# Unit.net
KiCad netlist of a schematic drawn in Altium Designer
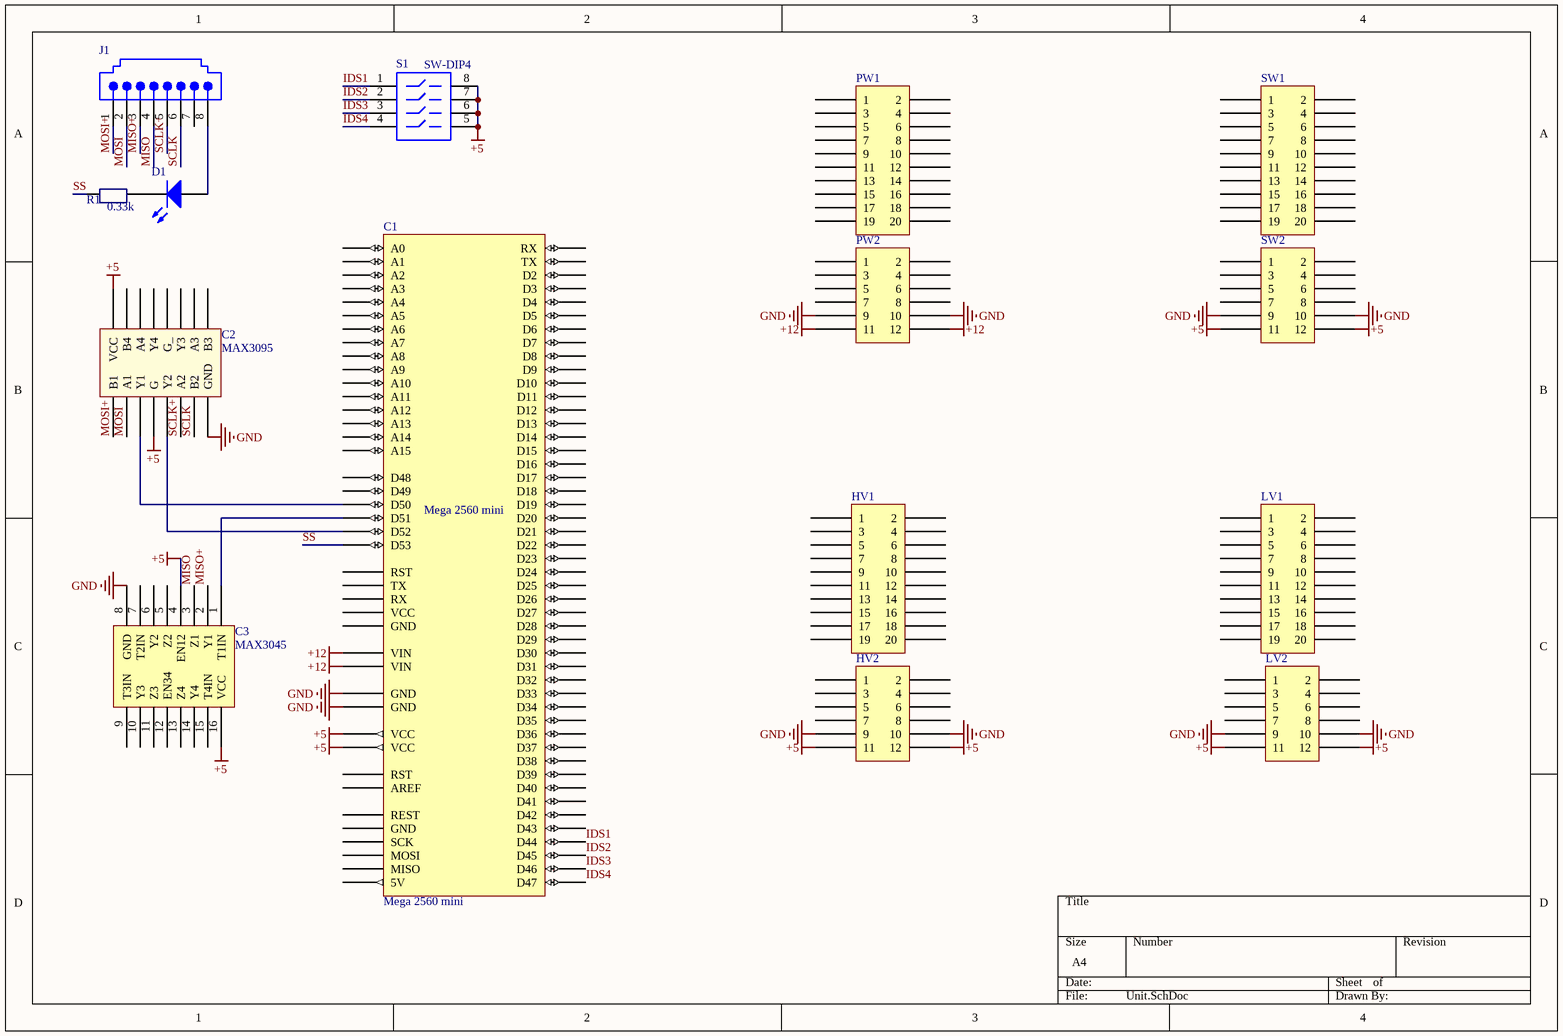
[diagram p0: Unit.SchDoc]

(export (version "E")
  (design (tool "Eeschema 10.0.6"))
  (components
    (comp (ref "C1")
      (value "Mega 2560 mini")
      (footprint "Mega 2560 mini")
      (libsource (lib "DeersADLib") (part "Mega 2560 mini"))
    )
    (comp (ref "C2") (value "MAX3095") (footprint "SOP16") (libsource (lib "DeersADLib") (part "MAX3095")))
    (comp (ref "C3")
      (value "MAX3045")
      (footprint "DeersADLib:TSSOP-16")
      (libsource (lib "DeersADLib") (part "MAX3045"))
    )
    (comp (ref "D1")
      (value "LED3")
      (footprint "3.5X2.8X1.9")
      (description "Typical BLUE SiC LED")
      (fields (field (name "PUBLISHER") "Altium Limited"))
      (libsource (lib "Miscellaneous Devices") (part "LED3"))
    )
    (comp (ref "HV1")
      (value "BTB-805-20P")
      (footprint "BTB-805-20P")
      (libsource (lib "DeersADLib") (part "BTB-805-20P"))
    )
    (comp (ref "HV2")
      (value "BTB-805-12P")
      (footprint "BTB-805-12P")
      (libsource (lib "DeersADLib") (part "BTB-805-12P"))
    )
    (comp (ref "J1")
      (value "15-43-6233")
      (footprint "15-43-6233")
      (description "Right Angle, Standard Profile, RJ45-Keyed, Flange Mount PCB Jack")
      (fields (field (name "PUBLISHER") "Altium Limited"))
      (libsource (lib "Molex Modular Jack Right Angle") (part "15-43-6233"))
    )
    (comp (ref "LV1")
      (value "BTB-805-20P")
      (footprint "BTB-805-20P")
      (libsource (lib "DeersADLib") (part "BTB-805-20P"))
    )
    (comp (ref "LV2")
      (value "BTB-805-12P")
      (footprint "BTB-805-12P")
      (libsource (lib "DeersADLib") (part "BTB-805-12P"))
    )
    (comp (ref "PW1")
      (value "BTB-805-20P")
      (footprint "BTB-805-20P")
      (libsource (lib "DeersADLib") (part "BTB-805-20P"))
    )
    (comp (ref "PW2")
      (value "BTB-805-12P")
      (footprint "BTB-805-12P")
      (libsource (lib "DeersADLib") (part "BTB-805-12P"))
    )
    (comp (ref "R1")
      (value "0.33k")
      (footprint "R0805")
      (libsource (lib "Common Device") (part "Resistance"))
    )
    (comp (ref "S1")
      (value "SW-DIP4")
      (footprint "DIP-8")
      (description "DIP Switch")
      (fields (field (name "PUBLISHER") "Altium Limited"))
      (libsource (lib "Miscellaneous Devices") (part "SW-DIP4"))
    )
    (comp (ref "SW1")
      (value "BTB-805-20P")
      (footprint "BTB-805-20P")
      (libsource (lib "DeersADLib") (part "BTB-805-20P"))
    )
    (comp (ref "SW2")
      (value "BTB-805-12P")
      (footprint "BTB-805-12P")
      (libsource (lib "DeersADLib") (part "BTB-805-12P"))
    )
  )
  (nets
    (net (code "1") (name "+5") (class "Default")
      (node (ref "C1") (pin "77") (pinfunction "VCC_77") (pintype "output"))
      (node (ref "C1") (pin "78") (pinfunction "VCC_78") (pintype "output"))
      (node (ref "C2") (pin "16") (pinfunction "VCC_16") (pintype "passive"))
      (node (ref "C2") (pin "4") (pinfunction "G_4") (pintype "passive"))
      (node (ref "C3") (pin "16") (pinfunction "VCC_16") (pintype "passive"))
      (node (ref "C3") (pin "4") (pinfunction "EN12_4") (pintype "passive"))
      (node (ref "HV2") (pin "11") (pinfunction "11_11") (pintype "passive"))
      (node (ref "HV2") (pin "12") (pinfunction "12_12") (pintype "passive"))
      (node (ref "LV2") (pin "11") (pinfunction "11_11") (pintype "passive"))
      (node (ref "LV2") (pin "12") (pinfunction "12_12") (pintype "passive"))
      (node (ref "S1") (pin "5") (pinfunction "5_5") (pintype "passive"))
      (node (ref "S1") (pin "6") (pinfunction "6_6") (pintype "passive"))
      (node (ref "S1") (pin "7") (pinfunction "7_7") (pintype "passive"))
      (node (ref "S1") (pin "8") (pinfunction "8_8") (pintype "passive"))
      (node (ref "SW2") (pin "11") (pinfunction "11_11") (pintype "passive"))
      (node (ref "SW2") (pin "12") (pinfunction "12_12") (pintype "passive"))
    )
    (net (code "2") (name "+12") (class "Default")
      (node (ref "C1") (pin "81") (pinfunction "VIN_81") (pintype "power_in"))
      (node (ref "C1") (pin "82") (pinfunction "VIN_82") (pintype "power_in"))
      (node (ref "PW2") (pin "11") (pinfunction "11_11") (pintype "passive"))
      (node (ref "PW2") (pin "12") (pinfunction "12_12") (pintype "passive"))
    )
    (net (code "3") (name "/IDS1") (class "Default")
      (node (ref "C1") (pin "60") (pinfunction "D44_60") (pintype "bidirectional"))
      (node (ref "S1") (pin "1") (pinfunction "1_1") (pintype "passive"))
    )
    (net (code "4") (name "/IDS2") (class "Default")
      (node (ref "C1") (pin "61") (pinfunction "D45_61") (pintype "bidirectional"))
      (node (ref "S1") (pin "2") (pinfunction "2_2") (pintype "passive"))
    )
    (net (code "5") (name "/IDS3") (class "Default")
      (node (ref "C1") (pin "62") (pinfunction "D46_62") (pintype "bidirectional"))
      (node (ref "S1") (pin "3") (pinfunction "3_3") (pintype "passive"))
    )
    (net (code "6") (name "/IDS4") (class "Default")
      (node (ref "C1") (pin "63") (pinfunction "D47_63") (pintype "bidirectional"))
      (node (ref "S1") (pin "4") (pinfunction "4_4") (pintype "passive"))
    )
    (net (code "7") (name "/MISO") (class "Default")
      (node (ref "C3") (pin "3") (pinfunction "Z1_3") (pintype "passive"))
      (node (ref "J1") (pin "4") (pinfunction "4_4") (pintype "passive"))
    )
    (net (code "8") (name "/MISO+") (class "Default")
      (node (ref "C3") (pin "2") (pinfunction "Y1_2") (pintype "passive"))
      (node (ref "J1") (pin "3") (pinfunction "3_3") (pintype "passive"))
    )
    (net (code "9") (name "/MOSI") (class "Default")
      (node (ref "C2") (pin "2") (pinfunction "A1_2") (pintype "passive"))
      (node (ref "J1") (pin "2") (pinfunction "2_2") (pintype "passive"))
    )
    (net (code "10") (name "/MOSI+") (class "Default")
      (node (ref "C2") (pin "1") (pinfunction "B1_1") (pintype "passive"))
      (node (ref "J1") (pin "1") (pinfunction "1_1") (pintype "passive"))
    )
    (net (code "11") (name "/SCLK") (class "Default")
      (node (ref "C2") (pin "7") (pinfunction "B2_7") (pintype "passive"))
      (node (ref "J1") (pin "6") (pinfunction "6_6") (pintype "passive"))
    )
    (net (code "12") (name "/SCLK+") (class "Default")
      (node (ref "C2") (pin "6") (pinfunction "A2_6") (pintype "passive"))
      (node (ref "J1") (pin "5") (pinfunction "5_5") (pintype "passive"))
    )
    (net (code "13") (name "/SS") (class "Default")
      (node (ref "C1") (pin "88") (pinfunction "D53_88") (pintype "bidirectional"))
      (node (ref "R1") (pin "1") (pintype "passive"))
    )
    (net (code "14") (name "GND") (class "Default")
      (node (ref "C1") (pin "79") (pinfunction "GND_79") (pintype "power_in"))
      (node (ref "C1") (pin "80") (pinfunction "GND_80") (pintype "power_in"))
      (node (ref "C2") (pin "8") (pinfunction "GND_8") (pintype "passive"))
      (node (ref "C3") (pin "8") (pinfunction "GND_8") (pintype "passive"))
      (node (ref "HV2") (pin "10") (pinfunction "10_10") (pintype "passive"))
      (node (ref "HV2") (pin "9") (pinfunction "9_9") (pintype "passive"))
      (node (ref "LV2") (pin "10") (pinfunction "10_10") (pintype "passive"))
      (node (ref "LV2") (pin "9") (pinfunction "9_9") (pintype "passive"))
      (node (ref "PW2") (pin "10") (pinfunction "10_10") (pintype "passive"))
      (node (ref "PW2") (pin "9") (pinfunction "9_9") (pintype "passive"))
      (node (ref "SW2") (pin "10") (pinfunction "10_10") (pintype "passive"))
      (node (ref "SW2") (pin "9") (pinfunction "9_9") (pintype "passive"))
    )
    (net (code "15") (name "Net-(C1-D50)") (class "Default")
      (node (ref "C1") (pin "85") (pinfunction "D50_85") (pintype "bidirectional"))
      (node (ref "C2") (pin "3") (pinfunction "Y1_3") (pintype "passive"))
    )
    (net (code "16") (name "Net-(C1-D51)") (class "Default")
      (node (ref "C1") (pin "86") (pinfunction "D51_86") (pintype "bidirectional"))
      (node (ref "C3") (pin "1") (pinfunction "T1IN_1") (pintype "passive"))
    )
    (net (code "17") (name "Net-(C1-D52)") (class "Default")
      (node (ref "C1") (pin "87") (pinfunction "D52_87") (pintype "bidirectional"))
      (node (ref "C2") (pin "5") (pinfunction "Y2_5") (pintype "passive"))
    )
    (net (code "18") (name "Net-(D1-A)") (class "Default")
      (node (ref "D1") (pin "1") (pinfunction "A_1") (pintype "passive"))
      (node (ref "J1") (pin "8") (pinfunction "8_8") (pintype "passive"))
    )
    (net (code "19") (name "Net-(D1-K)") (class "Default")
      (node (ref "D1") (pin "2") (pinfunction "K_2") (pintype "passive"))
      (node (ref "R1") (pin "2") (pintype "passive"))
    )
    (net (code "20") (name "unconnected-(C1-5V-Pad69)") (class "Default")
      (node (ref "C1") (pin "69") (pinfunction "5V_69") (pintype "output"))
    )
    (net (code "21") (name "unconnected-(C1-A0-Pad0)") (class "Default")
      (node (ref "C1") (pin "0") (pinfunction "A0_0") (pintype "bidirectional"))
    )
    (net (code "22") (name "unconnected-(C1-A1-Pad1)") (class "Default")
      (node (ref "C1") (pin "1") (pinfunction "A1_1") (pintype "bidirectional"))
    )
    (net (code "23") (name "unconnected-(C1-A2-Pad2)") (class "Default")
      (node (ref "C1") (pin "2") (pinfunction "A2_2") (pintype "bidirectional"))
    )
    (net (code "24") (name "unconnected-(C1-A3-Pad3)") (class "Default")
      (node (ref "C1") (pin "3") (pinfunction "A3_3") (pintype "bidirectional"))
    )
    (net (code "25") (name "unconnected-(C1-A4-Pad4)") (class "Default")
      (node (ref "C1") (pin "4") (pinfunction "A4_4") (pintype "bidirectional"))
    )
    (net (code "26") (name "unconnected-(C1-A5-Pad5)") (class "Default")
      (node (ref "C1") (pin "5") (pinfunction "A5_5") (pintype "bidirectional"))
    )
    (net (code "27") (name "unconnected-(C1-A6-Pad6)") (class "Default")
      (node (ref "C1") (pin "6") (pinfunction "A6_6") (pintype "bidirectional"))
    )
    (net (code "28") (name "unconnected-(C1-A7-Pad7)") (class "Default")
      (node (ref "C1") (pin "7") (pinfunction "A7_7") (pintype "bidirectional"))
    )
    (net (code "29") (name "unconnected-(C1-A8-Pad8)") (class "Default")
      (node (ref "C1") (pin "8") (pinfunction "A8_8") (pintype "bidirectional"))
    )
    (net (code "30") (name "unconnected-(C1-A9-Pad9)") (class "Default")
      (node (ref "C1") (pin "9") (pinfunction "A9_9") (pintype "bidirectional"))
    )
    (net (code "31") (name "unconnected-(C1-A10-Pad10)") (class "Default")
      (node (ref "C1") (pin "10") (pinfunction "A10_10") (pintype "bidirectional"))
    )
    (net (code "32") (name "unconnected-(C1-A11-Pad11)") (class "Default")
      (node (ref "C1") (pin "11") (pinfunction "A11_11") (pintype "bidirectional"))
    )
    (net (code "33") (name "unconnected-(C1-A12-Pad12)") (class "Default")
      (node (ref "C1") (pin "12") (pinfunction "A12_12") (pintype "bidirectional"))
    )
    (net (code "34") (name "unconnected-(C1-A13-Pad13)") (class "Default")
      (node (ref "C1") (pin "13") (pinfunction "A13_13") (pintype "bidirectional"))
    )
    (net (code "35") (name "unconnected-(C1-A14-Pad14)") (class "Default")
      (node (ref "C1") (pin "14") (pinfunction "A14_14") (pintype "bidirectional"))
    )
    (net (code "36") (name "unconnected-(C1-A15-Pad15)") (class "Default")
      (node (ref "C1") (pin "15") (pinfunction "A15_15") (pintype "bidirectional"))
    )
    (net (code "37") (name "unconnected-(C1-AREF-Pad75)") (class "Default")
      (node (ref "C1") (pin "75") (pinfunction "AREF_75") (pintype "passive"))
    )
    (net (code "38") (name "unconnected-(C1-D2-Pad18)") (class "Default")
      (node (ref "C1") (pin "18") (pinfunction "D2_18") (pintype "bidirectional"))
    )
    (net (code "39") (name "unconnected-(C1-D3-Pad19)") (class "Default")
      (node (ref "C1") (pin "19") (pinfunction "D3_19") (pintype "bidirectional"))
    )
    (net (code "40") (name "unconnected-(C1-D4-Pad20)") (class "Default")
      (node (ref "C1") (pin "20") (pinfunction "D4_20") (pintype "bidirectional"))
    )
    (net (code "41") (name "unconnected-(C1-D5-Pad21)") (class "Default")
      (node (ref "C1") (pin "21") (pinfunction "D5_21") (pintype "bidirectional"))
    )
    (net (code "42") (name "unconnected-(C1-D6-Pad22)") (class "Default")
      (node (ref "C1") (pin "22") (pinfunction "D6_22") (pintype "bidirectional"))
    )
    (net (code "43") (name "unconnected-(C1-D7-Pad23)") (class "Default")
      (node (ref "C1") (pin "23") (pinfunction "D7_23") (pintype "bidirectional"))
    )
    (net (code "44") (name "unconnected-(C1-D8-Pad24)") (class "Default")
      (node (ref "C1") (pin "24") (pinfunction "D8_24") (pintype "bidirectional"))
    )
    (net (code "45") (name "unconnected-(C1-D9-Pad25)") (class "Default")
      (node (ref "C1") (pin "25") (pinfunction "D9_25") (pintype "bidirectional"))
    )
    (net (code "46") (name "unconnected-(C1-D10-Pad26)") (class "Default")
      (node (ref "C1") (pin "26") (pinfunction "D10_26") (pintype "bidirectional"))
    )
    (net (code "47") (name "unconnected-(C1-D11-Pad27)") (class "Default")
      (node (ref "C1") (pin "27") (pinfunction "D11_27") (pintype "bidirectional"))
    )
    (net (code "48") (name "unconnected-(C1-D12-Pad28)") (class "Default")
      (node (ref "C1") (pin "28") (pinfunction "D12_28") (pintype "bidirectional"))
    )
    (net (code "49") (name "unconnected-(C1-D13-Pad29)") (class "Default")
      (node (ref "C1") (pin "29") (pinfunction "D13_29") (pintype "bidirectional"))
    )
    (net (code "50") (name "unconnected-(C1-D14-Pad30)") (class "Default")
      (node (ref "C1") (pin "30") (pinfunction "D14_30") (pintype "bidirectional"))
    )
    (net (code "51") (name "unconnected-(C1-D15-Pad31)") (class "Default")
      (node (ref "C1") (pin "31") (pinfunction "D15_31") (pintype "bidirectional"))
    )
    (net (code "52") (name "unconnected-(C1-D16-Pad32)") (class "Default")
      (node (ref "C1") (pin "32") (pinfunction "D16_32") (pintype "bidirectional"))
    )
    (net (code "53") (name "unconnected-(C1-D17-Pad33)") (class "Default")
      (node (ref "C1") (pin "33") (pinfunction "D17_33") (pintype "bidirectional"))
    )
    (net (code "54") (name "unconnected-(C1-D18-Pad34)") (class "Default")
      (node (ref "C1") (pin "34") (pinfunction "D18_34") (pintype "bidirectional"))
    )
    (net (code "55") (name "unconnected-(C1-D19-Pad35)") (class "Default")
      (node (ref "C1") (pin "35") (pinfunction "D19_35") (pintype "bidirectional"))
    )
    (net (code "56") (name "unconnected-(C1-D20-Pad36)") (class "Default")
      (node (ref "C1") (pin "36") (pinfunction "D20_36") (pintype "bidirectional"))
    )
    (net (code "57") (name "unconnected-(C1-D21-Pad37)") (class "Default")
      (node (ref "C1") (pin "37") (pinfunction "D21_37") (pintype "bidirectional"))
    )
    (net (code "58") (name "unconnected-(C1-D22-Pad38)") (class "Default")
      (node (ref "C1") (pin "38") (pinfunction "D22_38") (pintype "bidirectional"))
    )
    (net (code "59") (name "unconnected-(C1-D23-Pad39)") (class "Default")
      (node (ref "C1") (pin "39") (pinfunction "D23_39") (pintype "bidirectional"))
    )
    (net (code "60") (name "unconnected-(C1-D24-Pad40)") (class "Default")
      (node (ref "C1") (pin "40") (pinfunction "D24_40") (pintype "bidirectional"))
    )
    (net (code "61") (name "unconnected-(C1-D25-Pad41)") (class "Default")
      (node (ref "C1") (pin "41") (pinfunction "D25_41") (pintype "bidirectional"))
    )
    (net (code "62") (name "unconnected-(C1-D26-Pad42)") (class "Default")
      (node (ref "C1") (pin "42") (pinfunction "D26_42") (pintype "bidirectional"))
    )
    (net (code "63") (name "unconnected-(C1-D27-Pad43)") (class "Default")
      (node (ref "C1") (pin "43") (pinfunction "D27_43") (pintype "bidirectional"))
    )
    (net (code "64") (name "unconnected-(C1-D28-Pad44)") (class "Default")
      (node (ref "C1") (pin "44") (pinfunction "D28_44") (pintype "bidirectional"))
    )
    (net (code "65") (name "unconnected-(C1-D29-Pad45)") (class "Default")
      (node (ref "C1") (pin "45") (pinfunction "D29_45") (pintype "bidirectional"))
    )
    (net (code "66") (name "unconnected-(C1-D30-Pad46)") (class "Default")
      (node (ref "C1") (pin "46") (pinfunction "D30_46") (pintype "bidirectional"))
    )
    (net (code "67") (name "unconnected-(C1-D31-Pad47)") (class "Default")
      (node (ref "C1") (pin "47") (pinfunction "D31_47") (pintype "bidirectional"))
    )
    (net (code "68") (name "unconnected-(C1-D32-Pad48)") (class "Default")
      (node (ref "C1") (pin "48") (pinfunction "D32_48") (pintype "bidirectional"))
    )
    (net (code "69") (name "unconnected-(C1-D33-Pad49)") (class "Default")
      (node (ref "C1") (pin "49") (pinfunction "D33_49") (pintype "bidirectional"))
    )
    (net (code "70") (name "unconnected-(C1-D34-Pad50)") (class "Default")
      (node (ref "C1") (pin "50") (pinfunction "D34_50") (pintype "bidirectional"))
    )
    (net (code "71") (name "unconnected-(C1-D35-Pad51)") (class "Default")
      (node (ref "C1") (pin "51") (pinfunction "D35_51") (pintype "bidirectional"))
    )
    (net (code "72") (name "unconnected-(C1-D36-Pad52)") (class "Default")
      (node (ref "C1") (pin "52") (pinfunction "D36_52") (pintype "bidirectional"))
    )
    (net (code "73") (name "unconnected-(C1-D37-Pad53)") (class "Default")
      (node (ref "C1") (pin "53") (pinfunction "D37_53") (pintype "bidirectional"))
    )
    (net (code "74") (name "unconnected-(C1-D38-Pad54)") (class "Default")
      (node (ref "C1") (pin "54") (pinfunction "D38_54") (pintype "bidirectional"))
    )
    (net (code "75") (name "unconnected-(C1-D39-Pad55)") (class "Default")
      (node (ref "C1") (pin "55") (pinfunction "D39_55") (pintype "bidirectional"))
    )
    (net (code "76") (name "unconnected-(C1-D40-Pad56)") (class "Default")
      (node (ref "C1") (pin "56") (pinfunction "D40_56") (pintype "bidirectional"))
    )
    (net (code "77") (name "unconnected-(C1-D41-Pad57)") (class "Default")
      (node (ref "C1") (pin "57") (pinfunction "D41_57") (pintype "bidirectional"))
    )
    (net (code "78") (name "unconnected-(C1-D42-Pad58)") (class "Default")
      (node (ref "C1") (pin "58") (pinfunction "D42_58") (pintype "bidirectional"))
    )
    (net (code "79") (name "unconnected-(C1-D43-Pad59)") (class "Default")
      (node (ref "C1") (pin "59") (pinfunction "D43_59") (pintype "bidirectional"))
    )
    (net (code "80") (name "unconnected-(C1-D48-Pad83)") (class "Default")
      (node (ref "C1") (pin "83") (pinfunction "D48_83") (pintype "bidirectional"))
    )
    (net (code "81") (name "unconnected-(C1-D49-Pad84)") (class "Default")
      (node (ref "C1") (pin "84") (pinfunction "D49_84") (pintype "bidirectional"))
    )
    (net (code "82") (name "unconnected-(C1-GND-Pad68)") (class "Default")
      (node (ref "C1") (pin "68") (pinfunction "GND_68") (pintype "passive"))
    )
    (net (code "83") (name "unconnected-(C1-GND-Pad73)") (class "Default")
      (node (ref "C1") (pin "73") (pinfunction "GND_73") (pintype "passive"))
    )
    (net (code "84") (name "unconnected-(C1-MISO-Pad70)") (class "Default")
      (node (ref "C1") (pin "70") (pinfunction "MISO_70") (pintype "passive"))
    )
    (net (code "85") (name "unconnected-(C1-MOSI-Pad71)") (class "Default")
      (node (ref "C1") (pin "71") (pinfunction "MOSI_71") (pintype "passive"))
    )
    (net (code "86") (name "unconnected-(C1-REST-Pad74)") (class "Default")
      (node (ref "C1") (pin "74") (pinfunction "REST_74") (pintype "passive"))
    )
    (net (code "87") (name "unconnected-(C1-RST-Pad64)") (class "Default")
      (node (ref "C1") (pin "64") (pinfunction "RST_64") (pintype "passive"))
    )
    (net (code "88") (name "unconnected-(C1-RST-Pad76)") (class "Default")
      (node (ref "C1") (pin "76") (pinfunction "RST_76") (pintype "passive"))
    )
    (net (code "89") (name "unconnected-(C1-RX-Pad16)") (class "Default")
      (node (ref "C1") (pin "16") (pinfunction "RX_16") (pintype "bidirectional"))
    )
    (net (code "90") (name "unconnected-(C1-RX-Pad66)") (class "Default")
      (node (ref "C1") (pin "66") (pinfunction "RX_66") (pintype "passive"))
    )
    (net (code "91") (name "unconnected-(C1-SCK-Pad72)") (class "Default")
      (node (ref "C1") (pin "72") (pinfunction "SCK_72") (pintype "passive"))
    )
    (net (code "92") (name "unconnected-(C1-TX-Pad17)") (class "Default")
      (node (ref "C1") (pin "17") (pinfunction "TX_17") (pintype "bidirectional"))
    )
    (net (code "93") (name "unconnected-(C1-TX-Pad65)") (class "Default")
      (node (ref "C1") (pin "65") (pinfunction "TX_65") (pintype "passive"))
    )
    (net (code "94") (name "unconnected-(C1-VCC-Pad67)") (class "Default")
      (node (ref "C1") (pin "67") (pinfunction "VCC_67") (pintype "passive"))
    )
    (net (code "95") (name "unconnected-(C2-A3-Pad10)") (class "Default")
      (node (ref "C2") (pin "10") (pinfunction "A3_10") (pintype "passive"))
    )
    (net (code "96") (name "unconnected-(C2-A4-Pad14)") (class "Default")
      (node (ref "C2") (pin "14") (pinfunction "A4_14") (pintype "passive"))
    )
    (net (code "97") (name "unconnected-(C2-B3-Pad9)") (class "Default")
      (node (ref "C2") (pin "9") (pinfunction "B3_9") (pintype "passive"))
    )
    (net (code "98") (name "unconnected-(C2-B4-Pad15)") (class "Default")
      (node (ref "C2") (pin "15") (pinfunction "B4_15") (pintype "passive"))
    )
    (net (code "99") (name "unconnected-(C2-G_-Pad12)") (class "Default")
      (node (ref "C2") (pin "12") (pinfunction "G__12") (pintype "passive"))
    )
    (net (code "100") (name "unconnected-(C2-Y3-Pad11)") (class "Default")
      (node (ref "C2") (pin "11") (pinfunction "Y3_11") (pintype "passive"))
    )
    (net (code "101") (name "unconnected-(C2-Y4-Pad13)") (class "Default")
      (node (ref "C2") (pin "13") (pinfunction "Y4_13") (pintype "passive"))
    )
    (net (code "102") (name "unconnected-(C3-EN34-Pad12)") (class "Default")
      (node (ref "C3") (pin "12") (pinfunction "EN34_12") (pintype "passive"))
    )
    (net (code "103") (name "unconnected-(C3-T2IN-Pad7)") (class "Default")
      (node (ref "C3") (pin "7") (pinfunction "T2IN_7") (pintype "passive"))
    )
    (net (code "104") (name "unconnected-(C3-T3IN-Pad9)") (class "Default")
      (node (ref "C3") (pin "9") (pinfunction "T3IN_9") (pintype "passive"))
    )
    (net (code "105") (name "unconnected-(C3-T4IN-Pad15)") (class "Default")
      (node (ref "C3") (pin "15") (pinfunction "T4IN_15") (pintype "passive"))
    )
    (net (code "106") (name "unconnected-(C3-Y2-Pad6)") (class "Default")
      (node (ref "C3") (pin "6") (pinfunction "Y2_6") (pintype "passive"))
    )
    (net (code "107") (name "unconnected-(C3-Y3-Pad10)") (class "Default")
      (node (ref "C3") (pin "10") (pinfunction "Y3_10") (pintype "passive"))
    )
    (net (code "108") (name "unconnected-(C3-Y4-Pad14)") (class "Default")
      (node (ref "C3") (pin "14") (pinfunction "Y4_14") (pintype "passive"))
    )
    (net (code "109") (name "unconnected-(C3-Z2-Pad5)") (class "Default")
      (node (ref "C3") (pin "5") (pinfunction "Z2_5") (pintype "passive"))
    )
    (net (code "110") (name "unconnected-(C3-Z3-Pad11)") (class "Default")
      (node (ref "C3") (pin "11") (pinfunction "Z3_11") (pintype "passive"))
    )
    (net (code "111") (name "unconnected-(C3-Z4-Pad13)") (class "Default")
      (node (ref "C3") (pin "13") (pinfunction "Z4_13") (pintype "passive"))
    )
    (net (code "112") (name "unconnected-(HV1-Pad1)") (class "Default")
      (node (ref "HV1") (pin "1") (pinfunction "1_1") (pintype "passive"))
    )
    (net (code "113") (name "unconnected-(HV1-Pad2)") (class "Default")
      (node (ref "HV1") (pin "2") (pinfunction "2_2") (pintype "passive"))
    )
    (net (code "114") (name "unconnected-(HV1-Pad3)") (class "Default")
      (node (ref "HV1") (pin "3") (pinfunction "3_3") (pintype "passive"))
    )
    (net (code "115") (name "unconnected-(HV1-Pad4)") (class "Default")
      (node (ref "HV1") (pin "4") (pinfunction "4_4") (pintype "passive"))
    )
    (net (code "116") (name "unconnected-(HV1-Pad5)") (class "Default")
      (node (ref "HV1") (pin "5") (pinfunction "5_5") (pintype "passive"))
    )
    (net (code "117") (name "unconnected-(HV1-Pad6)") (class "Default")
      (node (ref "HV1") (pin "6") (pinfunction "6_6") (pintype "passive"))
    )
    (net (code "118") (name "unconnected-(HV1-Pad7)") (class "Default")
      (node (ref "HV1") (pin "7") (pinfunction "7_7") (pintype "passive"))
    )
    (net (code "119") (name "unconnected-(HV1-Pad8)") (class "Default")
      (node (ref "HV1") (pin "8") (pinfunction "8_8") (pintype "passive"))
    )
    (net (code "120") (name "unconnected-(HV1-Pad9)") (class "Default")
      (node (ref "HV1") (pin "9") (pinfunction "9_9") (pintype "passive"))
    )
    (net (code "121") (name "unconnected-(HV1-Pad10)") (class "Default")
      (node (ref "HV1") (pin "10") (pinfunction "10_10") (pintype "passive"))
    )
    (net (code "122") (name "unconnected-(HV1-Pad11)") (class "Default")
      (node (ref "HV1") (pin "11") (pinfunction "11_11") (pintype "passive"))
    )
    (net (code "123") (name "unconnected-(HV1-Pad12)") (class "Default")
      (node (ref "HV1") (pin "12") (pinfunction "12_12") (pintype "passive"))
    )
    (net (code "124") (name "unconnected-(HV1-Pad13)") (class "Default")
      (node (ref "HV1") (pin "13") (pinfunction "13_13") (pintype "passive"))
    )
    (net (code "125") (name "unconnected-(HV1-Pad14)") (class "Default")
      (node (ref "HV1") (pin "14") (pinfunction "14_14") (pintype "passive"))
    )
    (net (code "126") (name "unconnected-(HV1-Pad15)") (class "Default")
      (node (ref "HV1") (pin "15") (pinfunction "15_15") (pintype "passive"))
    )
    (net (code "127") (name "unconnected-(HV1-Pad16)") (class "Default")
      (node (ref "HV1") (pin "16") (pinfunction "16_16") (pintype "passive"))
    )
    (net (code "128") (name "unconnected-(HV1-Pad17)") (class "Default")
      (node (ref "HV1") (pin "17") (pinfunction "17_17") (pintype "passive"))
    )
    (net (code "129") (name "unconnected-(HV1-Pad18)") (class "Default")
      (node (ref "HV1") (pin "18") (pinfunction "18_18") (pintype "passive"))
    )
    (net (code "130") (name "unconnected-(HV1-Pad19)") (class "Default")
      (node (ref "HV1") (pin "19") (pinfunction "19_19") (pintype "passive"))
    )
    (net (code "131") (name "unconnected-(HV1-Pad20)") (class "Default")
      (node (ref "HV1") (pin "20") (pinfunction "20_20") (pintype "passive"))
    )
    (net (code "132") (name "unconnected-(HV2-Pad1)") (class "Default")
      (node (ref "HV2") (pin "1") (pinfunction "1_1") (pintype "passive"))
    )
    (net (code "133") (name "unconnected-(HV2-Pad2)") (class "Default")
      (node (ref "HV2") (pin "2") (pinfunction "2_2") (pintype "passive"))
    )
    (net (code "134") (name "unconnected-(HV2-Pad3)") (class "Default")
      (node (ref "HV2") (pin "3") (pinfunction "3_3") (pintype "passive"))
    )
    (net (code "135") (name "unconnected-(HV2-Pad4)") (class "Default")
      (node (ref "HV2") (pin "4") (pinfunction "4_4") (pintype "passive"))
    )
    (net (code "136") (name "unconnected-(HV2-Pad5)") (class "Default")
      (node (ref "HV2") (pin "5") (pinfunction "5_5") (pintype "passive"))
    )
    (net (code "137") (name "unconnected-(HV2-Pad6)") (class "Default")
      (node (ref "HV2") (pin "6") (pinfunction "6_6") (pintype "passive"))
    )
    (net (code "138") (name "unconnected-(HV2-Pad7)") (class "Default")
      (node (ref "HV2") (pin "7") (pinfunction "7_7") (pintype "passive"))
    )
    (net (code "139") (name "unconnected-(HV2-Pad8)") (class "Default")
      (node (ref "HV2") (pin "8") (pinfunction "8_8") (pintype "passive"))
    )
    (net (code "140") (name "unconnected-(J1-Pad7)") (class "Default")
      (node (ref "J1") (pin "7") (pinfunction "7_7") (pintype "passive"))
    )
    (net (code "141") (name "unconnected-(LV1-Pad1)") (class "Default")
      (node (ref "LV1") (pin "1") (pinfunction "1_1") (pintype "passive"))
    )
    (net (code "142") (name "unconnected-(LV1-Pad2)") (class "Default")
      (node (ref "LV1") (pin "2") (pinfunction "2_2") (pintype "passive"))
    )
    (net (code "143") (name "unconnected-(LV1-Pad3)") (class "Default")
      (node (ref "LV1") (pin "3") (pinfunction "3_3") (pintype "passive"))
    )
    (net (code "144") (name "unconnected-(LV1-Pad4)") (class "Default")
      (node (ref "LV1") (pin "4") (pinfunction "4_4") (pintype "passive"))
    )
    (net (code "145") (name "unconnected-(LV1-Pad5)") (class "Default")
      (node (ref "LV1") (pin "5") (pinfunction "5_5") (pintype "passive"))
    )
    (net (code "146") (name "unconnected-(LV1-Pad6)") (class "Default")
      (node (ref "LV1") (pin "6") (pinfunction "6_6") (pintype "passive"))
    )
    (net (code "147") (name "unconnected-(LV1-Pad7)") (class "Default")
      (node (ref "LV1") (pin "7") (pinfunction "7_7") (pintype "passive"))
    )
    (net (code "148") (name "unconnected-(LV1-Pad8)") (class "Default")
      (node (ref "LV1") (pin "8") (pinfunction "8_8") (pintype "passive"))
    )
    (net (code "149") (name "unconnected-(LV1-Pad9)") (class "Default")
      (node (ref "LV1") (pin "9") (pinfunction "9_9") (pintype "passive"))
    )
    (net (code "150") (name "unconnected-(LV1-Pad10)") (class "Default")
      (node (ref "LV1") (pin "10") (pinfunction "10_10") (pintype "passive"))
    )
    (net (code "151") (name "unconnected-(LV1-Pad11)") (class "Default")
      (node (ref "LV1") (pin "11") (pinfunction "11_11") (pintype "passive"))
    )
    (net (code "152") (name "unconnected-(LV1-Pad12)") (class "Default")
      (node (ref "LV1") (pin "12") (pinfunction "12_12") (pintype "passive"))
    )
    (net (code "153") (name "unconnected-(LV1-Pad13)") (class "Default")
      (node (ref "LV1") (pin "13") (pinfunction "13_13") (pintype "passive"))
    )
    (net (code "154") (name "unconnected-(LV1-Pad14)") (class "Default")
      (node (ref "LV1") (pin "14") (pinfunction "14_14") (pintype "passive"))
    )
    (net (code "155") (name "unconnected-(LV1-Pad15)") (class "Default")
      (node (ref "LV1") (pin "15") (pinfunction "15_15") (pintype "passive"))
    )
    (net (code "156") (name "unconnected-(LV1-Pad16)") (class "Default")
      (node (ref "LV1") (pin "16") (pinfunction "16_16") (pintype "passive"))
    )
    (net (code "157") (name "unconnected-(LV1-Pad17)") (class "Default")
      (node (ref "LV1") (pin "17") (pinfunction "17_17") (pintype "passive"))
    )
    (net (code "158") (name "unconnected-(LV1-Pad18)") (class "Default")
      (node (ref "LV1") (pin "18") (pinfunction "18_18") (pintype "passive"))
    )
    (net (code "159") (name "unconnected-(LV1-Pad19)") (class "Default")
      (node (ref "LV1") (pin "19") (pinfunction "19_19") (pintype "passive"))
    )
    (net (code "160") (name "unconnected-(LV1-Pad20)") (class "Default")
      (node (ref "LV1") (pin "20") (pinfunction "20_20") (pintype "passive"))
    )
    (net (code "161") (name "unconnected-(LV2-Pad1)") (class "Default")
      (node (ref "LV2") (pin "1") (pinfunction "1_1") (pintype "passive"))
    )
    (net (code "162") (name "unconnected-(LV2-Pad2)") (class "Default")
      (node (ref "LV2") (pin "2") (pinfunction "2_2") (pintype "passive"))
    )
    (net (code "163") (name "unconnected-(LV2-Pad3)") (class "Default")
      (node (ref "LV2") (pin "3") (pinfunction "3_3") (pintype "passive"))
    )
    (net (code "164") (name "unconnected-(LV2-Pad4)") (class "Default")
      (node (ref "LV2") (pin "4") (pinfunction "4_4") (pintype "passive"))
    )
    (net (code "165") (name "unconnected-(LV2-Pad5)") (class "Default")
      (node (ref "LV2") (pin "5") (pinfunction "5_5") (pintype "passive"))
    )
    (net (code "166") (name "unconnected-(LV2-Pad6)") (class "Default")
      (node (ref "LV2") (pin "6") (pinfunction "6_6") (pintype "passive"))
    )
    (net (code "167") (name "unconnected-(LV2-Pad7)") (class "Default")
      (node (ref "LV2") (pin "7") (pinfunction "7_7") (pintype "passive"))
    )
    (net (code "168") (name "unconnected-(LV2-Pad8)") (class "Default")
      (node (ref "LV2") (pin "8") (pinfunction "8_8") (pintype "passive"))
    )
    (net (code "169") (name "unconnected-(PW1-Pad1)") (class "Default")
      (node (ref "PW1") (pin "1") (pinfunction "1_1") (pintype "passive"))
    )
    (net (code "170") (name "unconnected-(PW1-Pad2)") (class "Default")
      (node (ref "PW1") (pin "2") (pinfunction "2_2") (pintype "passive"))
    )
    (net (code "171") (name "unconnected-(PW1-Pad3)") (class "Default")
      (node (ref "PW1") (pin "3") (pinfunction "3_3") (pintype "passive"))
    )
    (net (code "172") (name "unconnected-(PW1-Pad4)") (class "Default")
      (node (ref "PW1") (pin "4") (pinfunction "4_4") (pintype "passive"))
    )
    (net (code "173") (name "unconnected-(PW1-Pad5)") (class "Default")
      (node (ref "PW1") (pin "5") (pinfunction "5_5") (pintype "passive"))
    )
    (net (code "174") (name "unconnected-(PW1-Pad6)") (class "Default")
      (node (ref "PW1") (pin "6") (pinfunction "6_6") (pintype "passive"))
    )
    (net (code "175") (name "unconnected-(PW1-Pad7)") (class "Default")
      (node (ref "PW1") (pin "7") (pinfunction "7_7") (pintype "passive"))
    )
    (net (code "176") (name "unconnected-(PW1-Pad8)") (class "Default")
      (node (ref "PW1") (pin "8") (pinfunction "8_8") (pintype "passive"))
    )
    (net (code "177") (name "unconnected-(PW1-Pad9)") (class "Default")
      (node (ref "PW1") (pin "9") (pinfunction "9_9") (pintype "passive"))
    )
    (net (code "178") (name "unconnected-(PW1-Pad10)") (class "Default")
      (node (ref "PW1") (pin "10") (pinfunction "10_10") (pintype "passive"))
    )
    (net (code "179") (name "unconnected-(PW1-Pad11)") (class "Default")
      (node (ref "PW1") (pin "11") (pinfunction "11_11") (pintype "passive"))
    )
    (net (code "180") (name "unconnected-(PW1-Pad12)") (class "Default")
      (node (ref "PW1") (pin "12") (pinfunction "12_12") (pintype "passive"))
    )
    (net (code "181") (name "unconnected-(PW1-Pad13)") (class "Default")
      (node (ref "PW1") (pin "13") (pinfunction "13_13") (pintype "passive"))
    )
    (net (code "182") (name "unconnected-(PW1-Pad14)") (class "Default")
      (node (ref "PW1") (pin "14") (pinfunction "14_14") (pintype "passive"))
    )
    (net (code "183") (name "unconnected-(PW1-Pad15)") (class "Default")
      (node (ref "PW1") (pin "15") (pinfunction "15_15") (pintype "passive"))
    )
    (net (code "184") (name "unconnected-(PW1-Pad16)") (class "Default")
      (node (ref "PW1") (pin "16") (pinfunction "16_16") (pintype "passive"))
    )
    (net (code "185") (name "unconnected-(PW1-Pad17)") (class "Default")
      (node (ref "PW1") (pin "17") (pinfunction "17_17") (pintype "passive"))
    )
    (net (code "186") (name "unconnected-(PW1-Pad18)") (class "Default")
      (node (ref "PW1") (pin "18") (pinfunction "18_18") (pintype "passive"))
    )
    (net (code "187") (name "unconnected-(PW1-Pad19)") (class "Default")
      (node (ref "PW1") (pin "19") (pinfunction "19_19") (pintype "passive"))
    )
    (net (code "188") (name "unconnected-(PW1-Pad20)") (class "Default")
      (node (ref "PW1") (pin "20") (pinfunction "20_20") (pintype "passive"))
    )
    (net (code "189") (name "unconnected-(PW2-Pad1)") (class "Default")
      (node (ref "PW2") (pin "1") (pinfunction "1_1") (pintype "passive"))
    )
    (net (code "190") (name "unconnected-(PW2-Pad2)") (class "Default")
      (node (ref "PW2") (pin "2") (pinfunction "2_2") (pintype "passive"))
    )
    (net (code "191") (name "unconnected-(PW2-Pad3)") (class "Default")
      (node (ref "PW2") (pin "3") (pinfunction "3_3") (pintype "passive"))
    )
    (net (code "192") (name "unconnected-(PW2-Pad4)") (class "Default")
      (node (ref "PW2") (pin "4") (pinfunction "4_4") (pintype "passive"))
    )
    (net (code "193") (name "unconnected-(PW2-Pad5)") (class "Default")
      (node (ref "PW2") (pin "5") (pinfunction "5_5") (pintype "passive"))
    )
    (net (code "194") (name "unconnected-(PW2-Pad6)") (class "Default")
      (node (ref "PW2") (pin "6") (pinfunction "6_6") (pintype "passive"))
    )
    (net (code "195") (name "unconnected-(PW2-Pad7)") (class "Default")
      (node (ref "PW2") (pin "7") (pinfunction "7_7") (pintype "passive"))
    )
    (net (code "196") (name "unconnected-(PW2-Pad8)") (class "Default")
      (node (ref "PW2") (pin "8") (pinfunction "8_8") (pintype "passive"))
    )
    (net (code "197") (name "unconnected-(SW1-Pad1)") (class "Default")
      (node (ref "SW1") (pin "1") (pinfunction "1_1") (pintype "passive"))
    )
    (net (code "198") (name "unconnected-(SW1-Pad2)") (class "Default")
      (node (ref "SW1") (pin "2") (pinfunction "2_2") (pintype "passive"))
    )
    (net (code "199") (name "unconnected-(SW1-Pad3)") (class "Default")
      (node (ref "SW1") (pin "3") (pinfunction "3_3") (pintype "passive"))
    )
    (net (code "200") (name "unconnected-(SW1-Pad4)") (class "Default")
      (node (ref "SW1") (pin "4") (pinfunction "4_4") (pintype "passive"))
    )
    (net (code "201") (name "unconnected-(SW1-Pad5)") (class "Default")
      (node (ref "SW1") (pin "5") (pinfunction "5_5") (pintype "passive"))
    )
    (net (code "202") (name "unconnected-(SW1-Pad6)") (class "Default")
      (node (ref "SW1") (pin "6") (pinfunction "6_6") (pintype "passive"))
    )
    (net (code "203") (name "unconnected-(SW1-Pad7)") (class "Default")
      (node (ref "SW1") (pin "7") (pinfunction "7_7") (pintype "passive"))
    )
    (net (code "204") (name "unconnected-(SW1-Pad8)") (class "Default")
      (node (ref "SW1") (pin "8") (pinfunction "8_8") (pintype "passive"))
    )
    (net (code "205") (name "unconnected-(SW1-Pad9)") (class "Default")
      (node (ref "SW1") (pin "9") (pinfunction "9_9") (pintype "passive"))
    )
    (net (code "206") (name "unconnected-(SW1-Pad10)") (class "Default")
      (node (ref "SW1") (pin "10") (pinfunction "10_10") (pintype "passive"))
    )
    (net (code "207") (name "unconnected-(SW1-Pad11)") (class "Default")
      (node (ref "SW1") (pin "11") (pinfunction "11_11") (pintype "passive"))
    )
    (net (code "208") (name "unconnected-(SW1-Pad12)") (class "Default")
      (node (ref "SW1") (pin "12") (pinfunction "12_12") (pintype "passive"))
    )
    (net (code "209") (name "unconnected-(SW1-Pad13)") (class "Default")
      (node (ref "SW1") (pin "13") (pinfunction "13_13") (pintype "passive"))
    )
    (net (code "210") (name "unconnected-(SW1-Pad14)") (class "Default")
      (node (ref "SW1") (pin "14") (pinfunction "14_14") (pintype "passive"))
    )
    (net (code "211") (name "unconnected-(SW1-Pad15)") (class "Default")
      (node (ref "SW1") (pin "15") (pinfunction "15_15") (pintype "passive"))
    )
    (net (code "212") (name "unconnected-(SW1-Pad16)") (class "Default")
      (node (ref "SW1") (pin "16") (pinfunction "16_16") (pintype "passive"))
    )
    (net (code "213") (name "unconnected-(SW1-Pad17)") (class "Default")
      (node (ref "SW1") (pin "17") (pinfunction "17_17") (pintype "passive"))
    )
    (net (code "214") (name "unconnected-(SW1-Pad18)") (class "Default")
      (node (ref "SW1") (pin "18") (pinfunction "18_18") (pintype "passive"))
    )
    (net (code "215") (name "unconnected-(SW1-Pad19)") (class "Default")
      (node (ref "SW1") (pin "19") (pinfunction "19_19") (pintype "passive"))
    )
    (net (code "216") (name "unconnected-(SW1-Pad20)") (class "Default")
      (node (ref "SW1") (pin "20") (pinfunction "20_20") (pintype "passive"))
    )
    (net (code "217") (name "unconnected-(SW2-Pad1)") (class "Default")
      (node (ref "SW2") (pin "1") (pinfunction "1_1") (pintype "passive"))
    )
    (net (code "218") (name "unconnected-(SW2-Pad2)") (class "Default")
      (node (ref "SW2") (pin "2") (pinfunction "2_2") (pintype "passive"))
    )
    (net (code "219") (name "unconnected-(SW2-Pad3)") (class "Default")
      (node (ref "SW2") (pin "3") (pinfunction "3_3") (pintype "passive"))
    )
    (net (code "220") (name "unconnected-(SW2-Pad4)") (class "Default")
      (node (ref "SW2") (pin "4") (pinfunction "4_4") (pintype "passive"))
    )
    (net (code "221") (name "unconnected-(SW2-Pad5)") (class "Default")
      (node (ref "SW2") (pin "5") (pinfunction "5_5") (pintype "passive"))
    )
    (net (code "222") (name "unconnected-(SW2-Pad6)") (class "Default")
      (node (ref "SW2") (pin "6") (pinfunction "6_6") (pintype "passive"))
    )
    (net (code "223") (name "unconnected-(SW2-Pad7)") (class "Default")
      (node (ref "SW2") (pin "7") (pinfunction "7_7") (pintype "passive"))
    )
    (net (code "224") (name "unconnected-(SW2-Pad8)") (class "Default")
      (node (ref "SW2") (pin "8") (pinfunction "8_8") (pintype "passive"))
    )
  )
)
